# main.net
KiCad netlist of a schematic drawn in Altium Designer
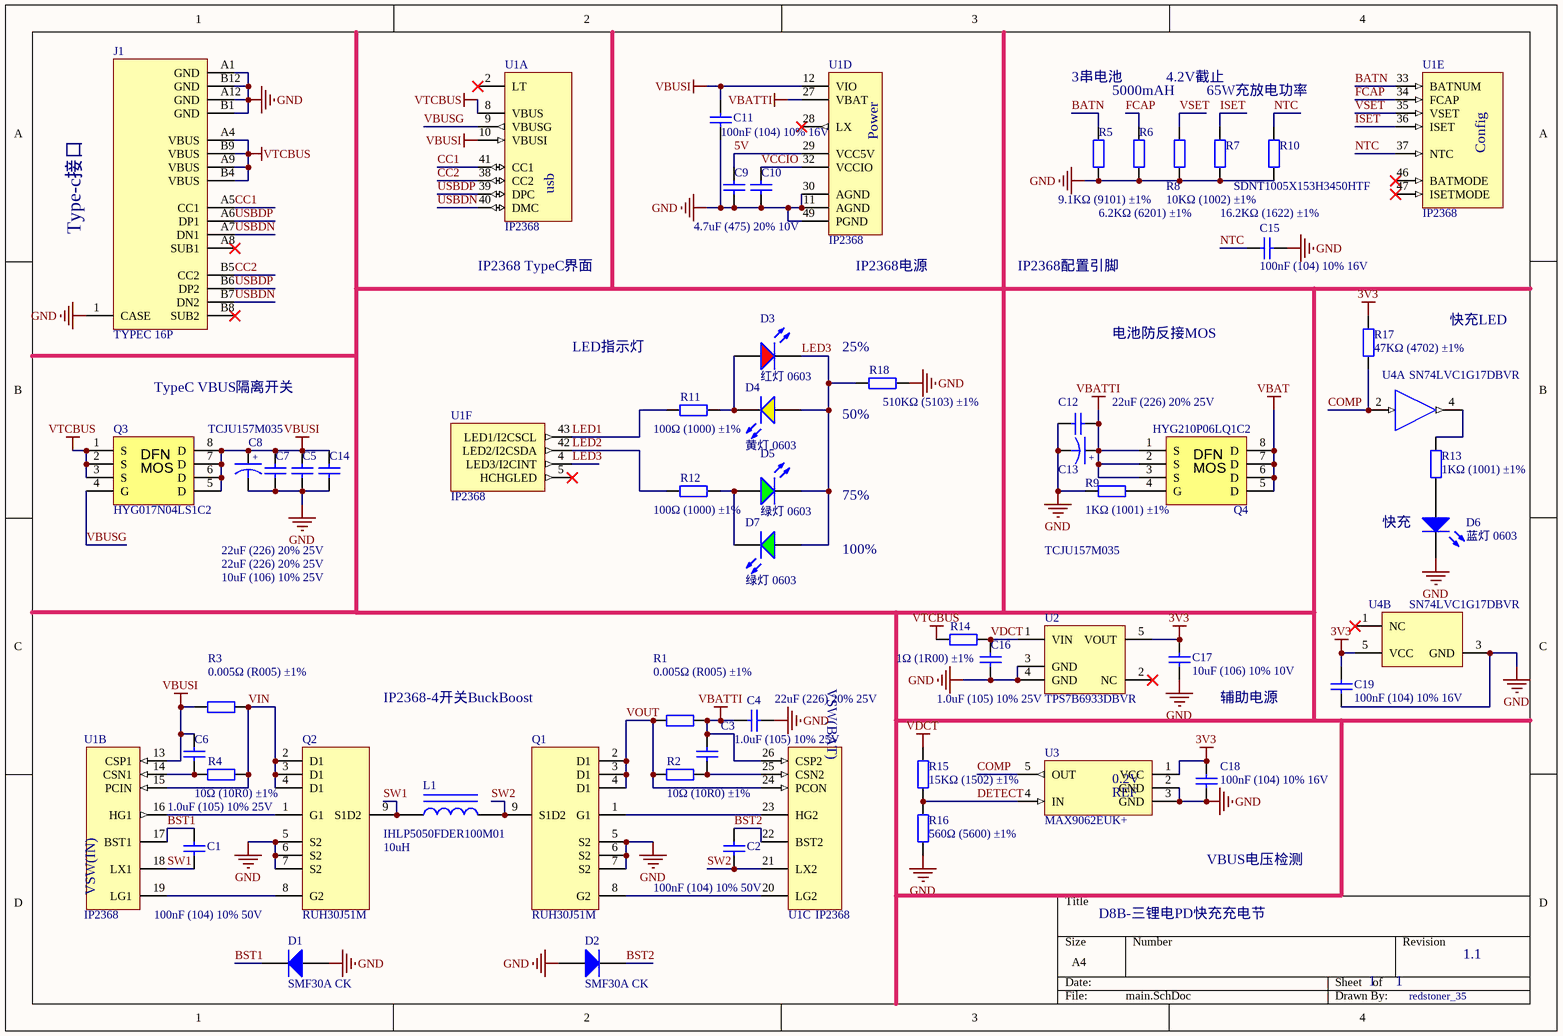
[diagram p0: main.SchDoc]

(export (version "E")
  (design (tool "Eeschema 10.0.6"))
  (components
    (comp (ref "C1")
      (value "100nF (104) 10% 50V")
      (footprint "0603_C")
      (description "贴片电容")
      (libsource (lib "Miscellaneous Devices LC") (part "0603 100nF (104) 10% 50V"))
    )
    (comp (ref "C2")
      (value "100nF (104) 10% 50V")
      (footprint "0603_C")
      (description "贴片电容")
      (libsource (lib "Miscellaneous Devices LC") (part "0603 100nF (104) 10% 50V"))
    )
    (comp (ref "C3")
      (value "1.0uF (105) 10% 25V")
      (footprint "0402_C")
      (description "贴片电容")
      (libsource (lib "Miscellaneous Devices LC") (part "0402 1.0uF (105) 10% 25V"))
    )
    (comp (ref "C4")
      (value "22uF (226) 20% 25V")
      (footprint "0805_C")
      (description "贴片电容")
      (libsource (lib "Miscellaneous Devices LC") (part "0805 22uF (226) 20% 25V"))
    )
    (comp (ref "C5")
      (value "22uF (226) 20% 25V")
      (footprint "0805_C")
      (description "贴片电容")
      (libsource (lib "Miscellaneous Devices LC") (part "0805 22uF (226) 20% 25V"))
    )
    (comp (ref "C6")
      (value "1.0uF (105) 10% 25V")
      (footprint "0402_C")
      (description "贴片电容")
      (libsource (lib "Miscellaneous Devices LC") (part "0402 1.0uF (105) 10% 25V"))
    )
    (comp (ref "C7")
      (value "22uF (226) 20% 25V")
      (footprint "0805_C")
      (description "贴片电容")
      (libsource (lib "Miscellaneous Devices LC") (part "0805 22uF (226) 20% 25V"))
    )
    (comp (ref "C8")
      (value "TCJU157M035")
      (footprint "CAPMP7362X41N")
      (description "Capacitor")
      (libsource (lib "山猫的集成库20190318") (part "CAP2"))
    )
    (comp (ref "C9")
      (value "4.7uF (475) 20% 10V")
      (footprint "0402_C")
      (description "贴片电容")
      (libsource (lib "Miscellaneous Devices LC") (part "0402 4.7uF (475) 20% 10V"))
    )
    (comp (ref "C10")
      (value "4.7uF (475) 20% 10V")
      (footprint "0402_C")
      (description "贴片电容")
      (libsource (lib "Miscellaneous Devices LC") (part "0402 4.7uF (475) 20% 10V"))
    )
    (comp (ref "C11")
      (value "100nF (104) 10% 16V")
      (footprint "0402_C")
      (description "贴片电容")
      (libsource (lib "Miscellaneous Devices LC") (part "0402 100nF (104) 10% 16V"))
    )
    (comp (ref "C12")
      (value "22uF (226) 20% 25V")
      (footprint "0805_C")
      (description "贴片电容")
      (libsource (lib "Miscellaneous Devices LC") (part "0805 22uF (226) 20% 25V"))
    )
    (comp (ref "C13")
      (value "TCJU157M035")
      (footprint "CAPMP7362X41N")
      (description "Capacitor")
      (libsource (lib "山猫的集成库20190318") (part "CAP2"))
    )
    (comp (ref "C14")
      (value "10uF (106) 10% 25V")
      (footprint "0805_C")
      (description "贴片电容")
      (libsource (lib "Miscellaneous Devices LC") (part "0805 10uF (106) 10% 25V"))
    )
    (comp (ref "C15")
      (value "100nF (104) 10% 16V")
      (footprint "0402_C")
      (description "贴片电容")
      (libsource (lib "Miscellaneous Devices LC") (part "0402 100nF (104) 10% 16V"))
    )
    (comp (ref "C16")
      (value "1.0uF (105) 10% 25V")
      (footprint "0402_C")
      (description "贴片电容")
      (libsource (lib "Miscellaneous Devices LC") (part "0402 1.0uF (105) 10% 25V"))
    )
    (comp (ref "C17")
      (value "10uF (106) 10% 10V")
      (footprint "0603_C")
      (description "贴片电容")
      (libsource (lib "Miscellaneous Devices LC") (part "0603 10uF (106) 10% 10V"))
    )
    (comp (ref "C18")
      (value "100nF (104) 10% 16V")
      (footprint "0402_C")
      (description "贴片电容")
      (libsource (lib "Miscellaneous Devices LC") (part "0402 100nF (104) 10% 16V"))
    )
    (comp (ref "C19")
      (value "100nF (104) 10% 16V")
      (footprint "0402_C")
      (description "贴片电容")
      (libsource (lib "Miscellaneous Devices LC") (part "0402 100nF (104) 10% 16V"))
    )
    (comp (ref "D1")
      (value "SMF30A CK")
      (footprint "SOD-123")
      (description "TVS二极管")
      (libsource (lib "Miscellaneous Devices LC") (part "SOD-123 B5819W  SL"))
    )
    (comp (ref "D2")
      (value "SMF30A CK")
      (footprint "SOD-123")
      (description "TVS二极管")
      (libsource (lib "Miscellaneous Devices LC") (part "SOD-123 B5819W  SL"))
    )
    (comp (ref "D3")
      (value "红灯 0603")
      (footprint "0603_LED_S1")
      (description "发光二极管")
      (libsource (lib "Miscellaneous Devices LC") (part "0603 红灯"))
    )
    (comp (ref "D4")
      (value "黄灯 0603")
      (footprint "0603_LED_S1")
      (description "发光二极管")
      (libsource (lib "Miscellaneous Devices LC") (part "0603 黄灯"))
    )
    (comp (ref "D5")
      (value "绿灯 0603")
      (footprint "0603_LED_S1")
      (description "发光二极管")
      (libsource (lib "Miscellaneous Devices LC") (part "0603 绿灯"))
    )
    (comp (ref "D6")
      (value "蓝灯 0603")
      (footprint "0603_LED_S1")
      (description "发光二极管")
      (libsource (lib "Miscellaneous Devices LC") (part "0603 蓝灯"))
    )
    (comp (ref "D7")
      (value "绿灯 0603")
      (footprint "0603_LED_S1")
      (description "发光二极管")
      (libsource (lib "Miscellaneous Devices LC") (part "0603 绿灯"))
    )
    (comp (ref "J1")
      (value "TYPEC 16P")
      (footprint "USB-C-SMD_KH-TYPE-C-16P")
      (description "16Pin TypeC立贴座子")
      (libsource (lib "custom") (part "KH-TYPEC-16P"))
    )
    (comp (ref "L1")
      (value "IHLP5050FDER100M01")
      (footprint "IHLP5050FDER***M01")
      (description "Vishay Inductor 10uH 16.4mR 15.5A")
      (fields (field (name "ALTIUM_VALUE") "10uH") (field (name "PUBLISHER") "Altium Limited"))
      (libsource (lib "Miscellaneous Devices") (part "Inductor Iron"))
    )
    (comp (ref "Q1")
      (value "RUH30J51M")
      (footprint "PDFN-8_L5.8-W4.9_RU30J30M")
      (description "Dual N MOSFET 30V/51A")
      (libsource (lib "custom") (part "RU30J30M"))
    )
    (comp (ref "Q2")
      (value "RUH30J51M")
      (footprint "PDFN-8_L5.8-W4.9_RU30J30M")
      (description "Dual N MOSFET 30V/51A")
      (libsource (lib "") (part "RU30J30M_1"))
    )
    (comp (ref "Q3")
      (value "HYG017N04LS1C2")
      (footprint "SON/DFN5x6(MOS)")
      (description "40V 1.7mΩ N Channel MOSFET")
      (libsource (lib "custom") (part "SON/DFN5x6 MOS"))
    )
    (comp (ref "Q4")
      (value "HYG210P06LQ1C2")
      (footprint "SON/DFN5x6(MOS)")
      (description "P Channel MOSFET -60V -40A 25mΩ")
      (libsource (lib "custom") (part "SON/DFN5x6 MOS"))
    )
    (comp (ref "R1")
      (value "0.005Ω (R005) ±1%")
      (footprint "1206_R")
      (description "贴片电阻")
      (libsource (lib "Miscellaneous Devices LC") (part "1206 0Ω (0R0) 1%"))
    )
    (comp (ref "R2")
      (value "10Ω (10R0) ±1%")
      (footprint "0402_R")
      (description "贴片电阻")
      (libsource (lib "Miscellaneous Devices LC") (part "0402 10Ω (10R0) 1%"))
    )
    (comp (ref "R3")
      (value "0.005Ω (R005) ±1%")
      (footprint "1206_R")
      (description "贴片电阻")
      (libsource (lib "Miscellaneous Devices LC") (part "1206 0Ω (0R0) 1%"))
    )
    (comp (ref "R4")
      (value "10Ω (10R0) ±1%")
      (footprint "0402_R")
      (description "贴片电阻")
      (libsource (lib "Miscellaneous Devices LC") (part "0402 10Ω (10R0) 1%"))
    )
    (comp (ref "R5")
      (value "9.1KΩ (9101) ±1%")
      (footprint "0402_R")
      (description "贴片电阻")
      (libsource (lib "Miscellaneous Devices LC") (part "0402 0Ω (0R0) 1%"))
    )
    (comp (ref "R6")
      (value "6.2KΩ (6201) ±1%")
      (footprint "0402_R")
      (description "贴片电阻")
      (libsource (lib "Miscellaneous Devices LC") (part "0402 0Ω (0R0) 1%"))
    )
    (comp (ref "R7")
      (value "16.2KΩ (1622) ±1%")
      (footprint "0402_R")
      (description "贴片电阻")
      (libsource (lib "Miscellaneous Devices LC") (part "0402 15KΩ (1502) 1%"))
    )
    (comp (ref "R8")
      (value "10KΩ (1002) ±1%")
      (footprint "0402_R")
      (description "贴片电阻")
      (libsource (lib "Miscellaneous Devices LC") (part "0402 10KΩ (1002) 1%"))
    )
    (comp (ref "R9")
      (value "1KΩ (1001) ±1%")
      (footprint "0402_R")
      (description "贴片电阻")
      (libsource (lib "Miscellaneous Devices LC") (part "0402 1KΩ (1001) 1%"))
    )
    (comp (ref "R10")
      (value "SDNT1005X153H3450HTF")
      (footprint "0402_R")
      (description "贴片NTC热敏电阻")
      (libsource (lib "Miscellaneous Devices LC") (part "0402 10KΩ (1002) 1%"))
    )
    (comp (ref "R11")
      (value "100Ω (1000) ±1%")
      (footprint "0603_R")
      (description "贴片电阻")
      (libsource (lib "Miscellaneous Devices LC") (part "0603 100Ω (1000) 1%"))
    )
    (comp (ref "R12")
      (value "100Ω (1000) ±1%")
      (footprint "0603_R")
      (description "贴片电阻")
      (libsource (lib "Miscellaneous Devices LC") (part "0603 100Ω (1000) 1%"))
    )
    (comp (ref "R13")
      (value "1KΩ (1001) ±1%")
      (footprint "0603_R")
      (description "贴片电阻")
      (libsource (lib "Miscellaneous Devices LC") (part "0603 1KΩ (1001) 1%"))
    )
    (comp (ref "R14")
      (value "1Ω (1R00) ±1%")
      (footprint "0402_R")
      (description "贴片电阻")
      (libsource (lib "Miscellaneous Devices LC") (part "0402 1Ω (1R00) 1%"))
    )
    (comp (ref "R15")
      (value "15KΩ (1502) ±1%")
      (footprint "0402_R")
      (description "贴片电阻")
      (libsource (lib "Miscellaneous Devices LC") (part "0402 15KΩ (1502) 1%"))
    )
    (comp (ref "R16")
      (value "560Ω (5600) ±1%")
      (footprint "0402_R")
      (description "贴片电阻")
      (libsource (lib "Miscellaneous Devices LC") (part "0402 510Ω (5100) 1%"))
    )
    (comp (ref "R17")
      (value "47KΩ (4702) ±1%")
      (footprint "0402_R")
      (description "贴片电阻")
      (libsource (lib "Miscellaneous Devices LC") (part "0402 47KΩ (4702) 1%"))
    )
    (comp (ref "R18")
      (value "510KΩ (5103) ±1%")
      (footprint "0402_R")
      (description "贴片电阻")
      (libsource (lib "Miscellaneous Devices LC") (part "0402 510KΩ (5103) 1%"))
    )
    (comp (ref "U1")
      (value "IP2368")
      (footprint "QFN50P700X700X100_HS-49M")
      (description "IP2368 2-5S 双向电池充放电管理，100W PD")
      (libsource (lib "custom") (part "IP2368"))
    )
    (comp (ref "U2")
      (value "TPS7B6933DBVR")
      (footprint "SOT95P245X110-5N")
      (description "150mA 40V max input Ultra low Iq LDO,fixed 3.3V output")
      (libsource (lib "custom") (part "TPS7B6933DBVR"))
    )
    (comp (ref "U3")
      (value "MAX9062EUK+")
      (footprint "SOT95P245X110-5N")
      (description "tiny Comparator with 0.2V Ref OD Output")
      (libsource (lib "custom") (part "MAX9062"))
    )
    (comp (ref "U4")
      (value "SN74LVC1G17DBVR")
      (footprint "DBV0005A_N")
      (description "Single Schmitt-Trigger Buffer, DBV0005A, LARGE T&R")
      (fields
        (field (name "GENERIC PART NUMBER") "SN74LVC1G17")
        (field (name "MANUFACTURER") "Texas Instruments")
      )
      (libsource (lib "TI_Logic_Little_Logic") (part "SN74LVC1G17DBVR"))
    )
  )
  (nets
    (net (code "1") (name "/5V") (class "Default")
      (node (ref "C9") (pin "2") (pinfunction "2_2") (pintype "passive"))
      (node (ref "U1") (pin "29") (pinfunction "VCC5V_29") (pintype "power_in"))
    )
    (net (code "2") (name "/BATN") (class "Default")
      (node (ref "R5") (pin "2") (pinfunction "2_2") (pintype "passive"))
      (node (ref "U1") (pin "33") (pinfunction "BATNUM_33") (pintype "input"))
    )
    (net (code "3") (name "/BST1") (class "Default")
      (node (ref "C1") (pin "2") (pinfunction "2_2") (pintype "passive"))
      (node (ref "D1") (pin "2") (pinfunction "K_2") (pintype "passive"))
      (node (ref "U1") (pin "17") (pinfunction "BST1_17") (pintype "power_in"))
    )
    (net (code "4") (name "/BST2") (class "Default")
      (node (ref "C2") (pin "2") (pinfunction "2_2") (pintype "passive"))
      (node (ref "D2") (pin "2") (pinfunction "K_2") (pintype "passive"))
      (node (ref "U1") (pin "22") (pinfunction "BST2_22") (pintype "power_in"))
    )
    (net (code "5") (name "/CC1") (class "Default")
      (node (ref "J1") (pin "A5") (pinfunction "CC1_A5") (pintype "passive"))
      (node (ref "U1") (pin "41") (pinfunction "CC1_41") (pintype "bidirectional"))
    )
    (net (code "6") (name "/CC2") (class "Default")
      (node (ref "J1") (pin "B5") (pinfunction "CC2_B5") (pintype "passive"))
      (node (ref "U1") (pin "38") (pinfunction "CC2_38") (pintype "bidirectional"))
    )
    (net (code "7") (name "/COMP") (class "Default")
      (node (ref "R17") (pin "1") (pinfunction "1_1") (pintype "passive"))
      (node (ref "U3") (pin "5") (pinfunction "OUT_5") (pintype "output"))
      (node (ref "U4") (pin "2") (pinfunction "A_2") (pintype "input"))
    )
    (net (code "8") (name "/DETECT") (class "Default")
      (node (ref "R15") (pin "1") (pinfunction "1_1") (pintype "passive"))
      (node (ref "R16") (pin "2") (pinfunction "2_2") (pintype "passive"))
      (node (ref "U3") (pin "4") (pinfunction "IN_4") (pintype "input"))
    )
    (net (code "9") (name "/FCAP") (class "Default")
      (node (ref "R6") (pin "2") (pinfunction "2_2") (pintype "passive"))
      (node (ref "U1") (pin "34") (pinfunction "FCAP_34") (pintype "input"))
    )
    (net (code "10") (name "/ISET") (class "Default")
      (node (ref "R7") (pin "2") (pinfunction "2_2") (pintype "passive"))
      (node (ref "U1") (pin "36") (pinfunction "ISET_36") (pintype "input"))
    )
    (net (code "11") (name "/LED1") (class "Default")
      (node (ref "R11") (pin "1") (pinfunction "1_1") (pintype "passive"))
      (node (ref "U1") (pin "43") (pinfunction "LED1/I2CSCL_43") (pintype "output"))
    )
    (net (code "12") (name "/LED2") (class "Default")
      (node (ref "R12") (pin "1") (pinfunction "1_1") (pintype "passive"))
      (node (ref "U1") (pin "42") (pinfunction "LED2/I2CSDA_42") (pintype "output"))
    )
    (net (code "13") (name "/LED3") (class "Default")
      (node (ref "D3") (pin "K") (pinfunction "K_K") (pintype "passive"))
      (node (ref "D4") (pin "A") (pinfunction "A_A") (pintype "passive"))
      (node (ref "D5") (pin "K") (pinfunction "K_K") (pintype "passive"))
      (node (ref "D7") (pin "A") (pinfunction "A_A") (pintype "passive"))
      (node (ref "R18") (pin "1") (pinfunction "1_1") (pintype "passive"))
      (node (ref "U1") (pin "4") (pinfunction "LED3/I2CINT_4") (pintype "output"))
    )
    (net (code "14") (name "/NTC") (class "Default")
      (node (ref "C15") (pin "1") (pinfunction "1_1") (pintype "passive"))
      (node (ref "R10") (pin "2") (pinfunction "2_2") (pintype "passive"))
      (node (ref "U1") (pin "37") (pinfunction "NTC_37") (pintype "input"))
    )
    (net (code "15") (name "/SW1") (class "Default")
      (node (ref "C1") (pin "1") (pinfunction "1_1") (pintype "passive"))
      (node (ref "L1") (pin "1") (pinfunction "1_1") (pintype "passive"))
      (node (ref "Q2") (pin "9") (pinfunction "S1D2_9") (pintype "passive"))
      (node (ref "U1") (pin "18") (pinfunction "LX1_18") (pintype "power_in"))
    )
    (net (code "16") (name "/SW2") (class "Default")
      (node (ref "C2") (pin "1") (pinfunction "1_1") (pintype "passive"))
      (node (ref "L1") (pin "2") (pinfunction "2_2") (pintype "passive"))
      (node (ref "Q1") (pin "9") (pinfunction "S1D2_9") (pintype "passive"))
      (node (ref "U1") (pin "21") (pinfunction "LX2_21") (pintype "power_in"))
    )
    (net (code "17") (name "/USBDN") (class "Default")
      (node (ref "J1") (pin "A7") (pinfunction "DN1_A7") (pintype "passive"))
      (node (ref "J1") (pin "B7") (pinfunction "DN2_B7") (pintype "passive"))
      (node (ref "U1") (pin "40") (pinfunction "DMC_40") (pintype "bidirectional"))
    )
    (net (code "18") (name "/USBDP") (class "Default")
      (node (ref "J1") (pin "A6") (pinfunction "DP1_A6") (pintype "passive"))
      (node (ref "J1") (pin "B6") (pinfunction "DP2_B6") (pintype "passive"))
      (node (ref "U1") (pin "39") (pinfunction "DPC_39") (pintype "bidirectional"))
    )
    (net (code "19") (name "/VBUSG") (class "Default")
      (node (ref "Q3") (pin "4") (pinfunction "G_4") (pintype "passive"))
      (node (ref "U1") (pin "9") (pinfunction "VBUSG_9") (pintype "output"))
    )
    (net (code "20") (name "/VCCIO") (class "Default")
      (node (ref "C10") (pin "2") (pinfunction "2_2") (pintype "passive"))
      (node (ref "U1") (pin "32") (pinfunction "VCCIO_32") (pintype "power_in"))
    )
    (net (code "21") (name "/VIN") (class "Default")
      (node (ref "Q2") (pin "2") (pinfunction "D1_2") (pintype "passive"))
      (node (ref "Q2") (pin "3") (pinfunction "D1_3") (pintype "passive"))
      (node (ref "Q2") (pin "4") (pinfunction "D1_4") (pintype "passive"))
      (node (ref "R3") (pin "2") (pinfunction "2_2") (pintype "passive"))
      (node (ref "R4") (pin "2") (pinfunction "2_2") (pintype "passive"))
      (node (ref "U1") (pin "15") (pinfunction "PCIN_15") (pintype "input"))
    )
    (net (code "22") (name "/VOUT") (class "Default")
      (node (ref "Q1") (pin "2") (pinfunction "D1_2") (pintype "passive"))
      (node (ref "Q1") (pin "3") (pinfunction "D1_3") (pintype "passive"))
      (node (ref "Q1") (pin "4") (pinfunction "D1_4") (pintype "passive"))
      (node (ref "R1") (pin "1") (pinfunction "1_1") (pintype "passive"))
      (node (ref "R2") (pin "1") (pinfunction "1_1") (pintype "passive"))
      (node (ref "U1") (pin "24") (pinfunction "PCON_24") (pintype "input"))
    )
    (net (code "23") (name "/VSET") (class "Default")
      (node (ref "R8") (pin "2") (pinfunction "2_2") (pintype "passive"))
      (node (ref "U1") (pin "35") (pinfunction "VSET_35") (pintype "input"))
    )
    (net (code "24") (name "3V3") (class "Default")
      (node (ref "C17") (pin "2") (pinfunction "2_2") (pintype "passive"))
      (node (ref "C18") (pin "2") (pinfunction "2_2") (pintype "passive"))
      (node (ref "C19") (pin "2") (pinfunction "2_2") (pintype "passive"))
      (node (ref "R17") (pin "2") (pinfunction "2_2") (pintype "passive"))
      (node (ref "U2") (pin "5") (pinfunction "VOUT_5") (pintype "power_in"))
      (node (ref "U3") (pin "1") (pinfunction "VCC_1") (pintype "power_in"))
      (node (ref "U4") (pin "5") (pinfunction "VCC_5") (pintype "power_in"))
    )
    (net (code "25") (name "GND") (class "Default")
      (node (ref "C10") (pin "1") (pinfunction "1_1") (pintype "passive"))
      (node (ref "C11") (pin "1") (pinfunction "1_1") (pintype "passive"))
      (node (ref "C12") (pin "2") (pinfunction "2_2") (pintype "passive"))
      (node (ref "C13") (pin "2") (pinfunction "2_2") (pintype "passive"))
      (node (ref "C14") (pin "1") (pinfunction "1_1") (pintype "passive"))
      (node (ref "C15") (pin "2") (pinfunction "2_2") (pintype "passive"))
      (node (ref "C16") (pin "1") (pinfunction "1_1") (pintype "passive"))
      (node (ref "C17") (pin "1") (pinfunction "1_1") (pintype "passive"))
      (node (ref "C18") (pin "1") (pinfunction "1_1") (pintype "passive"))
      (node (ref "C19") (pin "1") (pinfunction "1_1") (pintype "passive"))
      (node (ref "C4") (pin "2") (pinfunction "2_2") (pintype "passive"))
      (node (ref "C5") (pin "1") (pinfunction "1_1") (pintype "passive"))
      (node (ref "C7") (pin "1") (pinfunction "1_1") (pintype "passive"))
      (node (ref "C8") (pin "2") (pinfunction "2_2") (pintype "passive"))
      (node (ref "C9") (pin "1") (pinfunction "1_1") (pintype "passive"))
      (node (ref "D1") (pin "1") (pinfunction "A_1") (pintype "passive"))
      (node (ref "D2") (pin "1") (pinfunction "A_1") (pintype "passive"))
      (node (ref "D6") (pin "K") (pinfunction "K_K") (pintype "passive"))
      (node (ref "J1") (pin "1") (pinfunction "CASE_1") (pintype "passive"))
      (node (ref "J1") (pin "A1") (pinfunction "GND_A1") (pintype "passive"))
      (node (ref "J1") (pin "A12") (pinfunction "GND_A12") (pintype "passive"))
      (node (ref "J1") (pin "B1") (pinfunction "GND_B1") (pintype "passive"))
      (node (ref "J1") (pin "B12") (pinfunction "GND_B12") (pintype "passive"))
      (node (ref "Q1") (pin "5") (pinfunction "S2_5") (pintype "passive"))
      (node (ref "Q1") (pin "6") (pinfunction "S2_6") (pintype "passive"))
      (node (ref "Q1") (pin "7") (pinfunction "S2_7") (pintype "passive"))
      (node (ref "Q2") (pin "5") (pinfunction "S2_5") (pintype "passive"))
      (node (ref "Q2") (pin "6") (pinfunction "S2_6") (pintype "passive"))
      (node (ref "Q2") (pin "7") (pinfunction "S2_7") (pintype "passive"))
      (node (ref "R10") (pin "1") (pinfunction "1_1") (pintype "passive"))
      (node (ref "R16") (pin "1") (pinfunction "1_1") (pintype "passive"))
      (node (ref "R18") (pin "2") (pinfunction "2_2") (pintype "passive"))
      (node (ref "R5") (pin "1") (pinfunction "1_1") (pintype "passive"))
      (node (ref "R6") (pin "1") (pinfunction "1_1") (pintype "passive"))
      (node (ref "R7") (pin "1") (pinfunction "1_1") (pintype "passive"))
      (node (ref "R8") (pin "1") (pinfunction "1_1") (pintype "passive"))
      (node (ref "R9") (pin "1") (pinfunction "1_1") (pintype "passive"))
      (node (ref "U1") (pin "11") (pinfunction "AGND_11") (pintype "power_in"))
      (node (ref "U1") (pin "30") (pinfunction "AGND_30") (pintype "power_in"))
      (node (ref "U1") (pin "49") (pinfunction "PGND_49") (pintype "power_in"))
      (node (ref "U2") (pin "3") (pinfunction "GND_3") (pintype "power_in"))
      (node (ref "U2") (pin "4") (pinfunction "GND_4") (pintype "power_in"))
      (node (ref "U3") (pin "2") (pinfunction "GND_2") (pintype "power_in"))
      (node (ref "U3") (pin "3") (pinfunction "GND_3") (pintype "power_in"))
      (node (ref "U4") (pin "3") (pinfunction "GND_3") (pintype "power_in"))
    )
    (net (code "26") (name "Net-(D3-PadA)") (class "Default")
      (node (ref "D3") (pin "A") (pinfunction "A_A") (pintype "passive"))
      (node (ref "D4") (pin "K") (pinfunction "K_K") (pintype "passive"))
      (node (ref "R11") (pin "2") (pinfunction "2_2") (pintype "passive"))
    )
    (net (code "27") (name "Net-(D5-PadA)") (class "Default")
      (node (ref "D5") (pin "A") (pinfunction "A_A") (pintype "passive"))
      (node (ref "D7") (pin "K") (pinfunction "K_K") (pintype "passive"))
      (node (ref "R12") (pin "2") (pinfunction "2_2") (pintype "passive"))
    )
    (net (code "28") (name "Net-(D6-PadA)") (class "Default")
      (node (ref "D6") (pin "A") (pinfunction "A_A") (pintype "passive"))
      (node (ref "R13") (pin "1") (pinfunction "1_1") (pintype "passive"))
    )
    (net (code "29") (name "Net-(Q1-G1)") (class "Default")
      (node (ref "Q1") (pin "1") (pinfunction "G1_1") (pintype "passive"))
      (node (ref "U1") (pin "23") (pinfunction "HG2_23") (pintype "power_in"))
    )
    (net (code "30") (name "Net-(Q1-G2)") (class "Default")
      (node (ref "Q1") (pin "8") (pinfunction "G2_8") (pintype "passive"))
      (node (ref "U1") (pin "20") (pinfunction "LG2_20") (pintype "power_in"))
    )
    (net (code "31") (name "Net-(Q2-G1)") (class "Default")
      (node (ref "Q2") (pin "1") (pinfunction "G1_1") (pintype "passive"))
      (node (ref "U1") (pin "16") (pinfunction "HG1_16") (pintype "output"))
    )
    (net (code "32") (name "Net-(Q2-G2)") (class "Default")
      (node (ref "Q2") (pin "8") (pinfunction "G2_8") (pintype "passive"))
      (node (ref "U1") (pin "19") (pinfunction "LG1_19") (pintype "power_in"))
    )
    (net (code "33") (name "Net-(Q4-G)") (class "Default")
      (node (ref "Q4") (pin "4") (pinfunction "G_4") (pintype "passive"))
      (node (ref "R9") (pin "2") (pinfunction "2_2") (pintype "passive"))
    )
    (net (code "34") (name "Net-(U1B-CSN1)") (class "Default")
      (node (ref "C6") (pin "1") (pinfunction "1_1") (pintype "passive"))
      (node (ref "R4") (pin "1") (pinfunction "1_1") (pintype "passive"))
      (node (ref "U1") (pin "14") (pinfunction "CSN1_14") (pintype "input"))
    )
    (net (code "35") (name "Net-(U1C-CSN2)") (class "Default")
      (node (ref "C3") (pin "1") (pinfunction "1_1") (pintype "passive"))
      (node (ref "R2") (pin "2") (pinfunction "2_2") (pintype "passive"))
      (node (ref "U1") (pin "25") (pinfunction "CSN2_25") (pintype "input"))
    )
    (net (code "36") (name "Net-(U4A-Y)") (class "Default")
      (node (ref "R13") (pin "2") (pinfunction "2_2") (pintype "passive"))
      (node (ref "U4") (pin "4") (pinfunction "Y_4") (pintype "output"))
    )
    (net (code "37") (name "VBAT") (class "Default")
      (node (ref "Q4") (pin "5") (pinfunction "D_5") (pintype "passive"))
      (node (ref "Q4") (pin "6") (pinfunction "D_6") (pintype "passive"))
      (node (ref "Q4") (pin "7") (pinfunction "D_7") (pintype "passive"))
      (node (ref "Q4") (pin "8") (pinfunction "D_8") (pintype "passive"))
    )
    (net (code "38") (name "VBATTI") (class "Default")
      (node (ref "C12") (pin "1") (pinfunction "1_1") (pintype "passive"))
      (node (ref "C13") (pin "1") (pinfunction "1_1") (pintype "passive"))
      (node (ref "C3") (pin "2") (pinfunction "2_2") (pintype "passive"))
      (node (ref "C4") (pin "1") (pinfunction "1_1") (pintype "passive"))
      (node (ref "Q4") (pin "1") (pinfunction "S_1") (pintype "passive"))
      (node (ref "Q4") (pin "2") (pinfunction "S_2") (pintype "passive"))
      (node (ref "Q4") (pin "3") (pinfunction "S_3") (pintype "passive"))
      (node (ref "R1") (pin "2") (pinfunction "2_2") (pintype "passive"))
      (node (ref "U1") (pin "26") (pinfunction "CSP2_26") (pintype "input"))
      (node (ref "U1") (pin "27") (pinfunction "VBAT_27") (pintype "power_in"))
    )
    (net (code "39") (name "VBUSI") (class "Default")
      (node (ref "C11") (pin "2") (pinfunction "2_2") (pintype "passive"))
      (node (ref "C14") (pin "2") (pinfunction "2_2") (pintype "passive"))
      (node (ref "C5") (pin "2") (pinfunction "2_2") (pintype "passive"))
      (node (ref "C6") (pin "2") (pinfunction "2_2") (pintype "passive"))
      (node (ref "C7") (pin "2") (pinfunction "2_2") (pintype "passive"))
      (node (ref "C8") (pin "1") (pinfunction "1_1") (pintype "passive"))
      (node (ref "Q3") (pin "5") (pinfunction "D_5") (pintype "passive"))
      (node (ref "Q3") (pin "6") (pinfunction "D_6") (pintype "passive"))
      (node (ref "Q3") (pin "7") (pinfunction "D_7") (pintype "passive"))
      (node (ref "Q3") (pin "8") (pinfunction "D_8") (pintype "passive"))
      (node (ref "R3") (pin "1") (pinfunction "1_1") (pintype "passive"))
      (node (ref "U1") (pin "10") (pinfunction "VBUSI_10") (pintype "input"))
      (node (ref "U1") (pin "12") (pinfunction "VIO_12") (pintype "power_in"))
      (node (ref "U1") (pin "13") (pinfunction "CSP1_13") (pintype "input"))
    )
    (net (code "40") (name "VDCT") (class "Default")
      (node (ref "C16") (pin "2") (pinfunction "2_2") (pintype "passive"))
      (node (ref "R14") (pin "2") (pinfunction "2_2") (pintype "passive"))
      (node (ref "R15") (pin "2") (pinfunction "2_2") (pintype "passive"))
      (node (ref "U2") (pin "1") (pinfunction "VIN_1") (pintype "power_in"))
    )
    (net (code "41") (name "VTCBUS") (class "Default")
      (node (ref "J1") (pin "A4") (pinfunction "VBUS_A4") (pintype "passive"))
      (node (ref "J1") (pin "A9") (pinfunction "VBUS_A9") (pintype "passive"))
      (node (ref "J1") (pin "B4") (pinfunction "VBUS_B4") (pintype "passive"))
      (node (ref "J1") (pin "B9") (pinfunction "VBUS_B9") (pintype "passive"))
      (node (ref "Q3") (pin "1") (pinfunction "S_1") (pintype "passive"))
      (node (ref "Q3") (pin "2") (pinfunction "S_2") (pintype "passive"))
      (node (ref "Q3") (pin "3") (pinfunction "S_3") (pintype "passive"))
      (node (ref "R14") (pin "1") (pinfunction "1_1") (pintype "passive"))
      (node (ref "U1") (pin "8") (pinfunction "VBUS_8") (pintype "passive"))
    )
    (net (code "42") (name "unconnected-(J1-SUB1-PadA8)") (class "Default")
      (node (ref "J1") (pin "A8") (pinfunction "SUB1_A8") (pintype "passive+no_connect"))
    )
    (net (code "43") (name "unconnected-(J1-SUB2-PadB8)") (class "Default")
      (node (ref "J1") (pin "B8") (pinfunction "SUB2_B8") (pintype "passive+no_connect"))
    )
    (net (code "44") (name "unconnected-(U1A-LT-Pad2)") (class "Default")
      (node (ref "U1") (pin "2") (pinfunction "LT_2") (pintype "passive+no_connect"))
    )
    (net (code "45") (name "unconnected-(U1D-LX-Pad28)") (class "Default")
      (node (ref "U1") (pin "28") (pinfunction "LX_28") (pintype "output+no_connect"))
    )
    (net (code "46") (name "unconnected-(U1E-BATMODE-Pad46)") (class "Default")
      (node (ref "U1") (pin "46") (pinfunction "BATMODE_46") (pintype "input+no_connect"))
    )
    (net (code "47") (name "unconnected-(U1E-ISETMODE-Pad47)") (class "Default")
      (node (ref "U1") (pin "47") (pinfunction "ISETMODE_47") (pintype "input+no_connect"))
    )
    (net (code "48") (name "unconnected-(U1F-HCHGLED-Pad5)") (class "Default")
      (node (ref "U1") (pin "5") (pinfunction "HCHGLED_5") (pintype "output+no_connect"))
    )
    (net (code "49") (name "unconnected-(U2-NC-Pad2)") (class "Default")
      (node (ref "U2") (pin "2") (pinfunction "NC_2") (pintype "passive+no_connect"))
    )
    (net (code "50") (name "unconnected-(U4B-NC-Pad1)") (class "Default")
      (node (ref "U4") (pin "1") (pinfunction "NC_1") (pintype "passive+no_connect"))
    )
  )
)
